# SSOP-8_v10.net
KiCad netlist of a schematic drawn in EAGLE
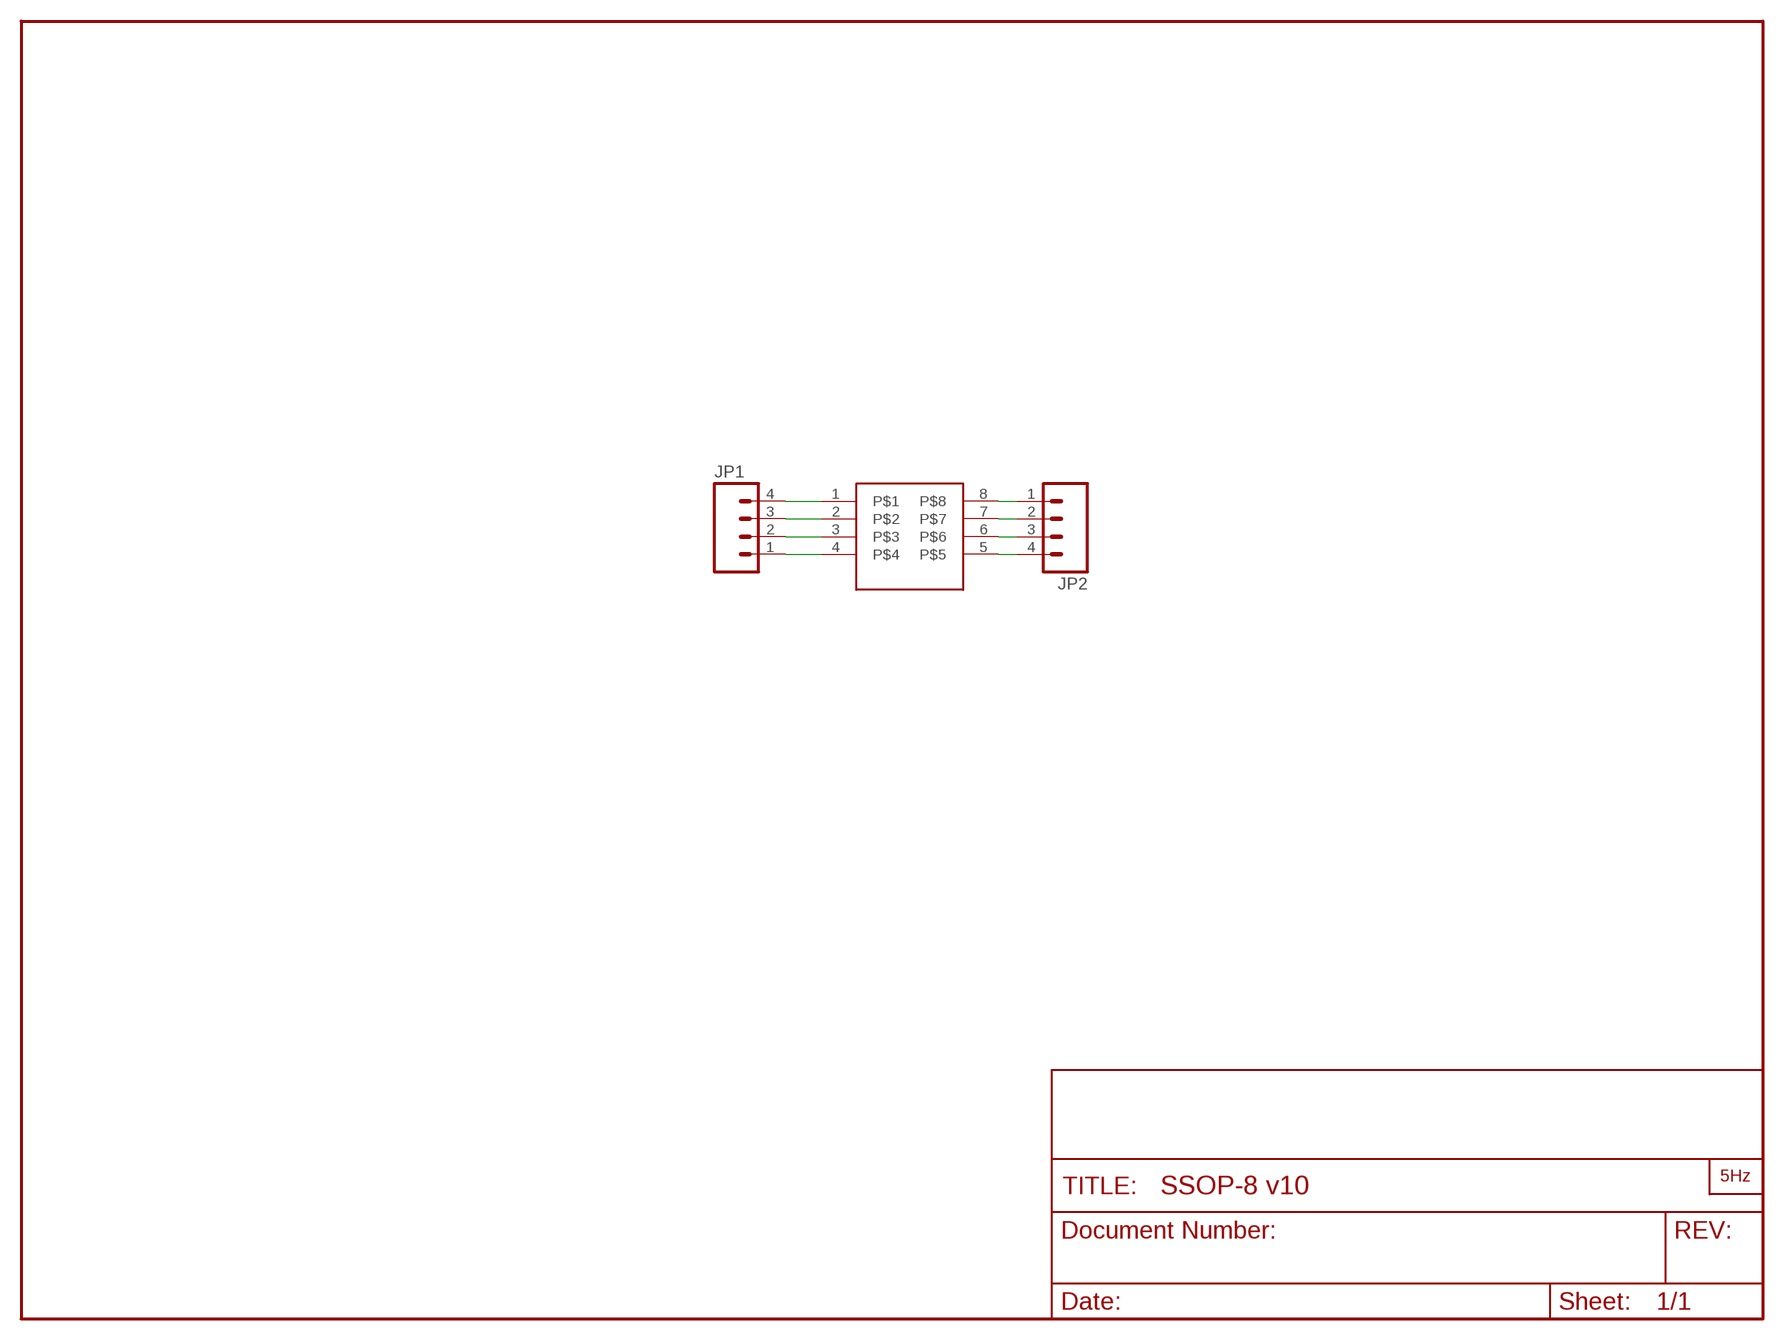
[diagram p0: schematic, sheet 1]

(export (version "E")
  (design (tool "Eeschema 10.0.6"))
  (components
    (comp (ref "JP1")
      (value "M04PTH")
      (footprint "eagle-import:1X04")
      (libsource (lib "eagle-import") (part "M04PTH"))
    )
    (comp (ref "JP2")
      (value "M04PTH")
      (footprint "eagle-import:1X04")
      (libsource (lib "eagle-import") (part "M04PTH"))
    )
    (comp (ref "U$1")
      (value "SSOP-8")
      (footprint "eagle-import:TSSOP8")
      (libsource (lib "eagle-import") (part "SSOP-8"))
    )
    (comp (ref "U$2")
      (value "LOGO2_SILKC5MM")
      (footprint "eagle-import:CIRCULO2_5MM")
      (libsource (lib "eagle-import") (part "LOGO2_SILKC5MM"))
    )
  )
  (nets
    (net (code "1") (name "Net-(U$1-P$1)") (class "Default")
      (node (ref "JP1") (pin "4") (pinfunction "4_4") (pintype "passive"))
      (node (ref "U$1") (pin "1") (pinfunction "P$1_1") (pintype "bidirectional"))
    )
    (net (code "2") (name "Net-(U$1-P$2)") (class "Default")
      (node (ref "JP1") (pin "3") (pinfunction "3_3") (pintype "passive"))
      (node (ref "U$1") (pin "2") (pinfunction "P$2_2") (pintype "bidirectional"))
    )
    (net (code "3") (name "Net-(U$1-P$3)") (class "Default")
      (node (ref "JP1") (pin "2") (pinfunction "2_2") (pintype "passive"))
      (node (ref "U$1") (pin "3") (pinfunction "P$3_3") (pintype "bidirectional"))
    )
    (net (code "4") (name "Net-(U$1-P$4)") (class "Default")
      (node (ref "JP1") (pin "1") (pinfunction "1_1") (pintype "passive"))
      (node (ref "U$1") (pin "4") (pinfunction "P$4_4") (pintype "bidirectional"))
    )
    (net (code "5") (name "Net-(U$1-P$5)") (class "Default")
      (node (ref "JP2") (pin "4") (pinfunction "4_4") (pintype "passive"))
      (node (ref "U$1") (pin "5") (pinfunction "P$5_5") (pintype "bidirectional"))
    )
    (net (code "6") (name "Net-(U$1-P$6)") (class "Default")
      (node (ref "JP2") (pin "3") (pinfunction "3_3") (pintype "passive"))
      (node (ref "U$1") (pin "6") (pinfunction "P$6_6") (pintype "bidirectional"))
    )
    (net (code "7") (name "Net-(U$1-P$7)") (class "Default")
      (node (ref "JP2") (pin "2") (pinfunction "2_2") (pintype "passive"))
      (node (ref "U$1") (pin "7") (pinfunction "P$7_7") (pintype "bidirectional"))
    )
    (net (code "8") (name "Net-(U$1-P$8)") (class "Default")
      (node (ref "JP2") (pin "1") (pinfunction "1_1") (pintype "passive"))
      (node (ref "U$1") (pin "8") (pinfunction "P$8_8") (pintype "bidirectional"))
    )
  )
)
